# shema_v6.net
KiCad netlist of a schematic drawn in EAGLE
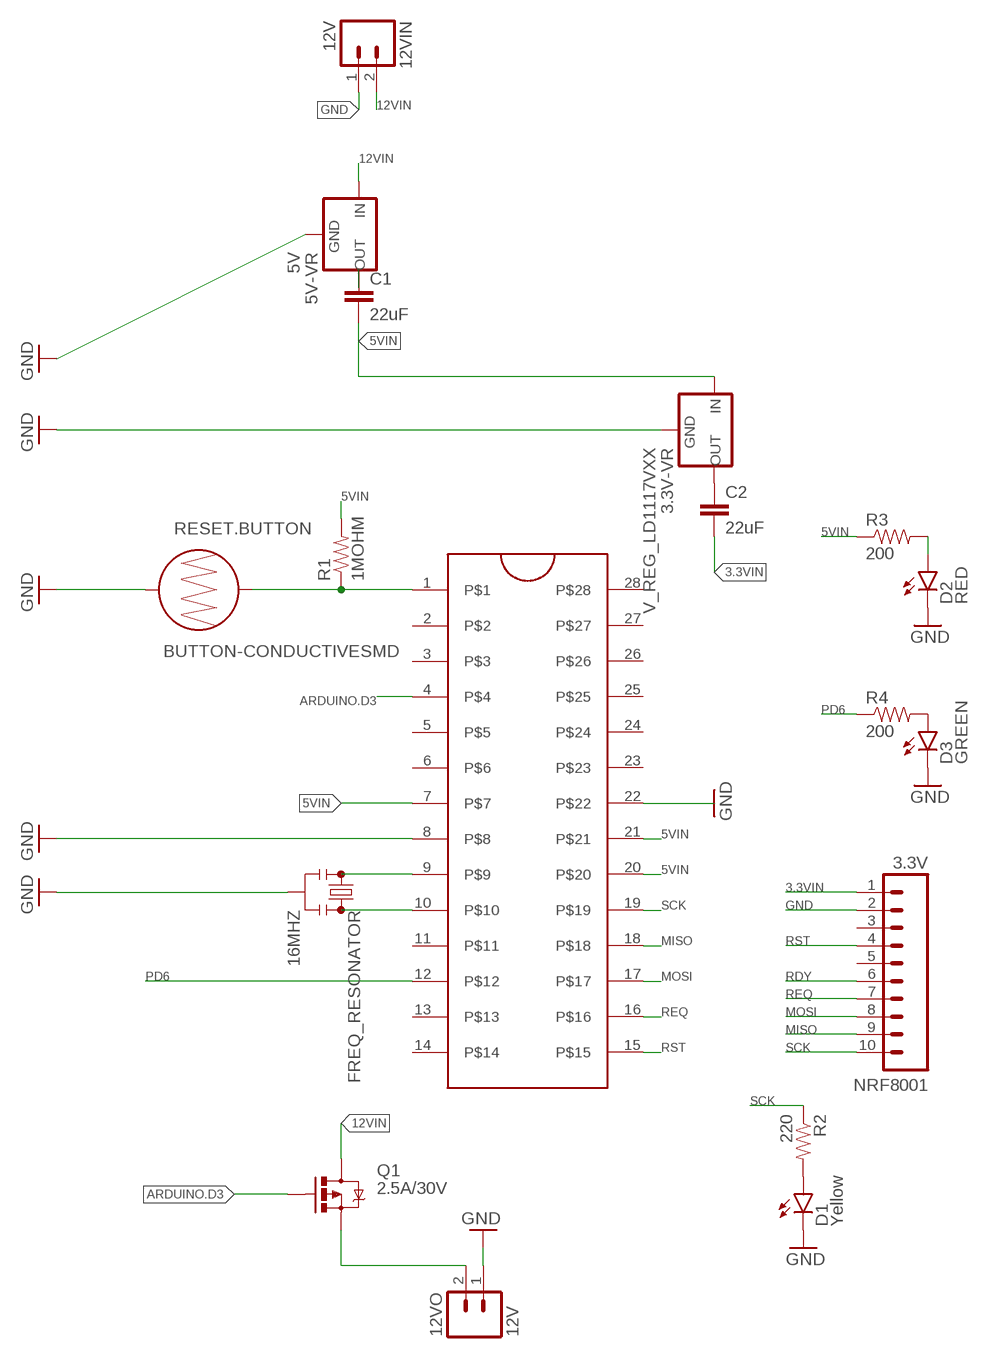
[diagram p0: schematic, sheet 1]

(export (version "E")
  (design (tool "Eeschema 10.0.6"))
  (components
    (comp (ref "3.3V-VR")
      (value "V_REG_LD1117VXX")
      (footprint "eagle-import:78XXL")
      (libsource (lib "eagle-import") (part "V_REG_LD1117VXX"))
    )
    (comp (ref "5V-VR")
      (value "5V")
      (footprint "eagle-import:TO-220-ALT")
      (libsource (lib "eagle-import") (part "V_REG_78XX-TO-220"))
    )
    (comp (ref "12VIN")
      (value "12V")
      (footprint "eagle-import:JST-2-PTH")
      (libsource (lib "eagle-import") (part "M02JST-PTH-2"))
    )
    (comp (ref "12VO")
      (value "12V")
      (footprint "eagle-import:JST-2-PTH")
      (libsource (lib "eagle-import") (part "M02JST-PTH-2"))
    )
    (comp (ref "ATMEGA328")
      (value "ZIFSOCKET-28-3ZIFFSOCKET-28-3")
      (footprint "eagle-import:DIL28-3-ZIF_SOCKET")
      (libsource (lib "eagle-import") (part "ZIFSOCKET-28-3ZIFFSOCKET-28-3"))
    )
    (comp (ref "C1")
      (value "22uF")
      (footprint "eagle-import:1210")
      (libsource (lib "eagle-import") (part "22UF-16V-20%-(1210)"))
    )
    (comp (ref "C2")
      (value "22uF")
      (footprint "eagle-import:1210")
      (libsource (lib "eagle-import") (part "22UF-16V-20%-(1210)"))
    )
    (comp (ref "D1")
      (value "Yellow")
      (footprint "eagle-import:LED-0603")
      (libsource (lib "eagle-import") (part "LED-YELLOW0603"))
    )
    (comp (ref "D2")
      (value "RED")
      (footprint "eagle-import:LED-0603")
      (libsource (lib "eagle-import") (part "LED-RED0603"))
    )
    (comp (ref "D3")
      (value "GREEN")
      (footprint "eagle-import:LED-1206")
      (libsource (lib "eagle-import") (part "LED-GREEN1206"))
    )
    (comp (ref "FREQ_RESONATOR")
      (value "16MHZ")
      (footprint "eagle-import:RESONATOR-SMD")
      (libsource (lib "eagle-import") (part "RESONATOR16MHZ"))
    )
    (comp (ref "NRF8001")
      (value "3.3V")
      (footprint "eagle-import:1X10")
      (libsource (lib "eagle-import") (part "M10SILK_FEMALE_PTH"))
    )
    (comp (ref "Q1")
      (value "2.5A/30V")
      (footprint "eagle-import:SOT23-3")
      (libsource (lib "eagle-import") (part "MOSFET-PCHANNELDMG2307L"))
    )
    (comp (ref "R1")
      (value "1MOHM")
      (footprint "eagle-import:1_6W-RES")
      (libsource (lib "eagle-import") (part "RESISTORPTH-1/6W"))
    )
    (comp (ref "R2")
      (value "220")
      (footprint "eagle-import:AXIAL-0.3EZ")
      (libsource (lib "eagle-import") (part "100OHM-1/4W-1%(PTH)HORIZ-KIT"))
    )
    (comp (ref "R3")
      (value "200")
      (footprint "eagle-import:0603-RES")
      (libsource (lib "eagle-import") (part "200OHM1/10W1%(0603)"))
    )
    (comp (ref "R4")
      (value "200")
      (footprint "eagle-import:0603-RES")
      (libsource (lib "eagle-import") (part "200OHM1/10W1%(0603)"))
    )
    (comp (ref "RESET.BUTTON")
      (value "BUTTON-CONDUCTIVESMD")
      (footprint "eagle-import:BUTTON-CONDUCTIVE")
      (libsource (lib "eagle-import") (part "BUTTON-CONDUCTIVESMD"))
    )
  )
  (nets
    (net (code "1") (name "/MISO") (class "Default")
      (node (ref "ATMEGA328") (pin "18") (pinfunction "P$18_18") (pintype "bidirectional"))
      (node (ref "NRF8001") (pin "9") (pinfunction "9_9") (pintype "passive"))
    )
    (net (code "2") (name "/MOSI") (class "Default")
      (node (ref "ATMEGA328") (pin "17") (pinfunction "P$17_17") (pintype "bidirectional"))
      (node (ref "NRF8001") (pin "8") (pinfunction "8_8") (pintype "passive"))
    )
    (net (code "3") (name "/PD6") (class "Default")
      (node (ref "ATMEGA328") (pin "12") (pinfunction "P$12_12") (pintype "bidirectional"))
      (node (ref "R4") (pin "1") (pinfunction "1_1") (pintype "passive"))
    )
    (net (code "4") (name "/RDY") (class "Default")
      (node (ref "NRF8001") (pin "6") (pinfunction "6_6") (pintype "passive"))
    )
    (net (code "5") (name "/REQ") (class "Default")
      (node (ref "ATMEGA328") (pin "16") (pinfunction "P$16_16") (pintype "bidirectional"))
      (node (ref "NRF8001") (pin "7") (pinfunction "7_7") (pintype "passive"))
    )
    (net (code "6") (name "/RST") (class "Default")
      (node (ref "ATMEGA328") (pin "15") (pinfunction "P$15_15") (pintype "bidirectional"))
      (node (ref "NRF8001") (pin "4") (pinfunction "4_4") (pintype "passive"))
    )
    (net (code "7") (name "/SCK") (class "Default")
      (node (ref "ATMEGA328") (pin "19") (pinfunction "P$19_19") (pintype "bidirectional"))
      (node (ref "NRF8001") (pin "10") (pinfunction "10_10") (pintype "passive"))
      (node (ref "R2") (pin "P$1") (pinfunction "1_P$1") (pintype "passive"))
    )
    (net (code "8") (name "3.3VIN") (class "Default")
      (node (ref "C2") (pin "2") (pinfunction "2_2") (pintype "passive"))
      (node (ref "NRF8001") (pin "1") (pinfunction "1_1") (pintype "passive"))
    )
    (net (code "9") (name "5VIN") (class "Default")
      (node (ref "3.3V-VR") (pin "OUT") (pinfunction "IN_OUT") (pintype "input"))
      (node (ref "ATMEGA328") (pin "20") (pinfunction "P$20_20") (pintype "bidirectional"))
      (node (ref "ATMEGA328") (pin "21") (pinfunction "P$21_21") (pintype "bidirectional"))
      (node (ref "ATMEGA328") (pin "7") (pinfunction "P$7_7") (pintype "bidirectional"))
      (node (ref "C1") (pin "2") (pinfunction "2_2") (pintype "passive"))
      (node (ref "R1") (pin "2") (pinfunction "2_2") (pintype "passive"))
      (node (ref "R3") (pin "1") (pinfunction "1_1") (pintype "passive"))
    )
    (net (code "10") (name "12VIN") (class "Default")
      (node (ref "12VIN") (pin "2") (pinfunction "2_2") (pintype "passive"))
      (node (ref "5V-VR") (pin "IN") (pinfunction "IN_IN") (pintype "input"))
      (node (ref "Q1") (pin "3") (pinfunction "D_3") (pintype "passive"))
    )
    (net (code "11") (name "ARDUINO.D3") (class "Default")
      (node (ref "ATMEGA328") (pin "4") (pinfunction "P$4_4") (pintype "bidirectional"))
      (node (ref "Q1") (pin "1") (pinfunction "G_1") (pintype "passive"))
    )
    (net (code "12") (name "GND") (class "Default")
      (node (ref "12VIN") (pin "1") (pinfunction "1_1") (pintype "passive"))
      (node (ref "12VO") (pin "1") (pinfunction "1_1") (pintype "passive"))
      (node (ref "3.3V-VR") (pin "IN") (pinfunction "GND_IN") (pintype "input"))
      (node (ref "5V-VR") (pin "GND") (pinfunction "GND_GND") (pintype "input"))
      (node (ref "ATMEGA328") (pin "8") (pinfunction "P$8_8") (pintype "bidirectional"))
      (node (ref "D1") (pin "C") (pinfunction "C_C") (pintype "passive"))
      (node (ref "D2") (pin "C") (pinfunction "C_C") (pintype "passive"))
      (node (ref "D3") (pin "C") (pinfunction "C_C") (pintype "passive"))
      (node (ref "FREQ_RESONATOR") (pin "2") (pinfunction "2_2") (pintype "passive"))
      (node (ref "NRF8001") (pin "2") (pinfunction "2_2") (pintype "passive"))
      (node (ref "RESET.BUTTON") (pin "1") (pinfunction "1_1") (pintype "passive"))
    )
    (net (code "13") (name "Net-(3.3V-VR-OUT)") (class "Default")
      (node (ref "3.3V-VR") (pin "GND") (pinfunction "OUT_GND") (pintype "passive"))
      (node (ref "C2") (pin "1") (pinfunction "1_1") (pintype "passive"))
    )
    (net (code "14") (name "Net-(5V-VR-PadOUT)") (class "Default")
      (node (ref "5V-VR") (pin "OUT") (pinfunction "OUT_OUT") (pintype "passive"))
      (node (ref "C1") (pin "1") (pinfunction "1_1") (pintype "passive"))
    )
    (net (code "15") (name "Net-(ATMEGA328-P$1)") (class "Default")
      (node (ref "ATMEGA328") (pin "1") (pinfunction "P$1_1") (pintype "bidirectional"))
      (node (ref "R1") (pin "1") (pinfunction "1_1") (pintype "passive"))
      (node (ref "RESET.BUTTON") (pin "2") (pinfunction "2_2") (pintype "passive"))
    )
    (net (code "16") (name "Net-(ATMEGA328-P$9)") (class "Default")
      (node (ref "ATMEGA328") (pin "9") (pinfunction "P$9_9") (pintype "bidirectional"))
      (node (ref "FREQ_RESONATOR") (pin "1") (pinfunction "1_1") (pintype "passive"))
    )
    (net (code "17") (name "Net-(ATMEGA328-P$10)") (class "Default")
      (node (ref "ATMEGA328") (pin "10") (pinfunction "P$10_10") (pintype "bidirectional"))
      (node (ref "FREQ_RESONATOR") (pin "3") (pinfunction "3_3") (pintype "passive"))
    )
    (net (code "18") (name "Net-(D2-PadA)") (class "Default")
      (node (ref "D2") (pin "A") (pinfunction "A_A") (pintype "passive"))
      (node (ref "R3") (pin "2") (pinfunction "2_2") (pintype "passive"))
    )
    (net (code "19") (name "Net-(D3-PadA)") (class "Default")
      (node (ref "D3") (pin "A") (pinfunction "A_A") (pintype "passive"))
      (node (ref "R4") (pin "2") (pinfunction "2_2") (pintype "passive"))
    )
    (net (code "20") (name "Net-(Q1-S)") (class "Default")
      (node (ref "12VO") (pin "2") (pinfunction "2_2") (pintype "passive"))
      (node (ref "Q1") (pin "2") (pinfunction "S_2") (pintype "passive"))
    )
    (net (code "21") (name "Net-(R2-2)") (class "Default")
      (node (ref "D1") (pin "A") (pinfunction "A_A") (pintype "passive"))
      (node (ref "R2") (pin "P$2") (pinfunction "2_P$2") (pintype "passive"))
    )
    (net (code "22") (name "unconnected-(ATMEGA328-P$2-Pad2)") (class "Default")
      (node (ref "ATMEGA328") (pin "2") (pinfunction "P$2_2") (pintype "bidirectional"))
    )
    (net (code "23") (name "unconnected-(ATMEGA328-P$3-Pad3)") (class "Default")
      (node (ref "ATMEGA328") (pin "3") (pinfunction "P$3_3") (pintype "bidirectional"))
    )
    (net (code "24") (name "unconnected-(ATMEGA328-P$5-Pad5)") (class "Default")
      (node (ref "ATMEGA328") (pin "5") (pinfunction "P$5_5") (pintype "bidirectional"))
    )
    (net (code "25") (name "unconnected-(ATMEGA328-P$6-Pad6)") (class "Default")
      (node (ref "ATMEGA328") (pin "6") (pinfunction "P$6_6") (pintype "bidirectional"))
    )
    (net (code "26") (name "unconnected-(ATMEGA328-P$11-Pad11)") (class "Default")
      (node (ref "ATMEGA328") (pin "11") (pinfunction "P$11_11") (pintype "bidirectional"))
    )
    (net (code "27") (name "unconnected-(ATMEGA328-P$13-Pad13)") (class "Default")
      (node (ref "ATMEGA328") (pin "13") (pinfunction "P$13_13") (pintype "bidirectional"))
    )
    (net (code "28") (name "unconnected-(ATMEGA328-P$14-Pad14)") (class "Default")
      (node (ref "ATMEGA328") (pin "14") (pinfunction "P$14_14") (pintype "bidirectional"))
    )
    (net (code "29") (name "unconnected-(ATMEGA328-P$22-Pad22)") (class "Default")
      (node (ref "ATMEGA328") (pin "22") (pinfunction "P$22_22") (pintype "bidirectional"))
    )
    (net (code "30") (name "unconnected-(ATMEGA328-P$23-Pad23)") (class "Default")
      (node (ref "ATMEGA328") (pin "23") (pinfunction "P$23_23") (pintype "bidirectional"))
    )
    (net (code "31") (name "unconnected-(ATMEGA328-P$24-Pad24)") (class "Default")
      (node (ref "ATMEGA328") (pin "24") (pinfunction "P$24_24") (pintype "bidirectional"))
    )
    (net (code "32") (name "unconnected-(ATMEGA328-P$25-Pad25)") (class "Default")
      (node (ref "ATMEGA328") (pin "25") (pinfunction "P$25_25") (pintype "bidirectional"))
    )
    (net (code "33") (name "unconnected-(ATMEGA328-P$26-Pad26)") (class "Default")
      (node (ref "ATMEGA328") (pin "26") (pinfunction "P$26_26") (pintype "bidirectional"))
    )
    (net (code "34") (name "unconnected-(ATMEGA328-P$27-Pad27)") (class "Default")
      (node (ref "ATMEGA328") (pin "27") (pinfunction "P$27_27") (pintype "bidirectional"))
    )
    (net (code "35") (name "unconnected-(ATMEGA328-P$28-Pad28)") (class "Default")
      (node (ref "ATMEGA328") (pin "28") (pinfunction "P$28_28") (pintype "bidirectional"))
    )
    (net (code "36") (name "unconnected-(NRF8001-Pad3)") (class "Default")
      (node (ref "NRF8001") (pin "3") (pinfunction "3_3") (pintype "passive"))
    )
    (net (code "37") (name "unconnected-(NRF8001-Pad5)") (class "Default")
      (node (ref "NRF8001") (pin "5") (pinfunction "5_5") (pintype "passive"))
    )
  )
)
